# DIGITAL_IO.net
KiCad netlist of a schematic drawn in Altium Designer
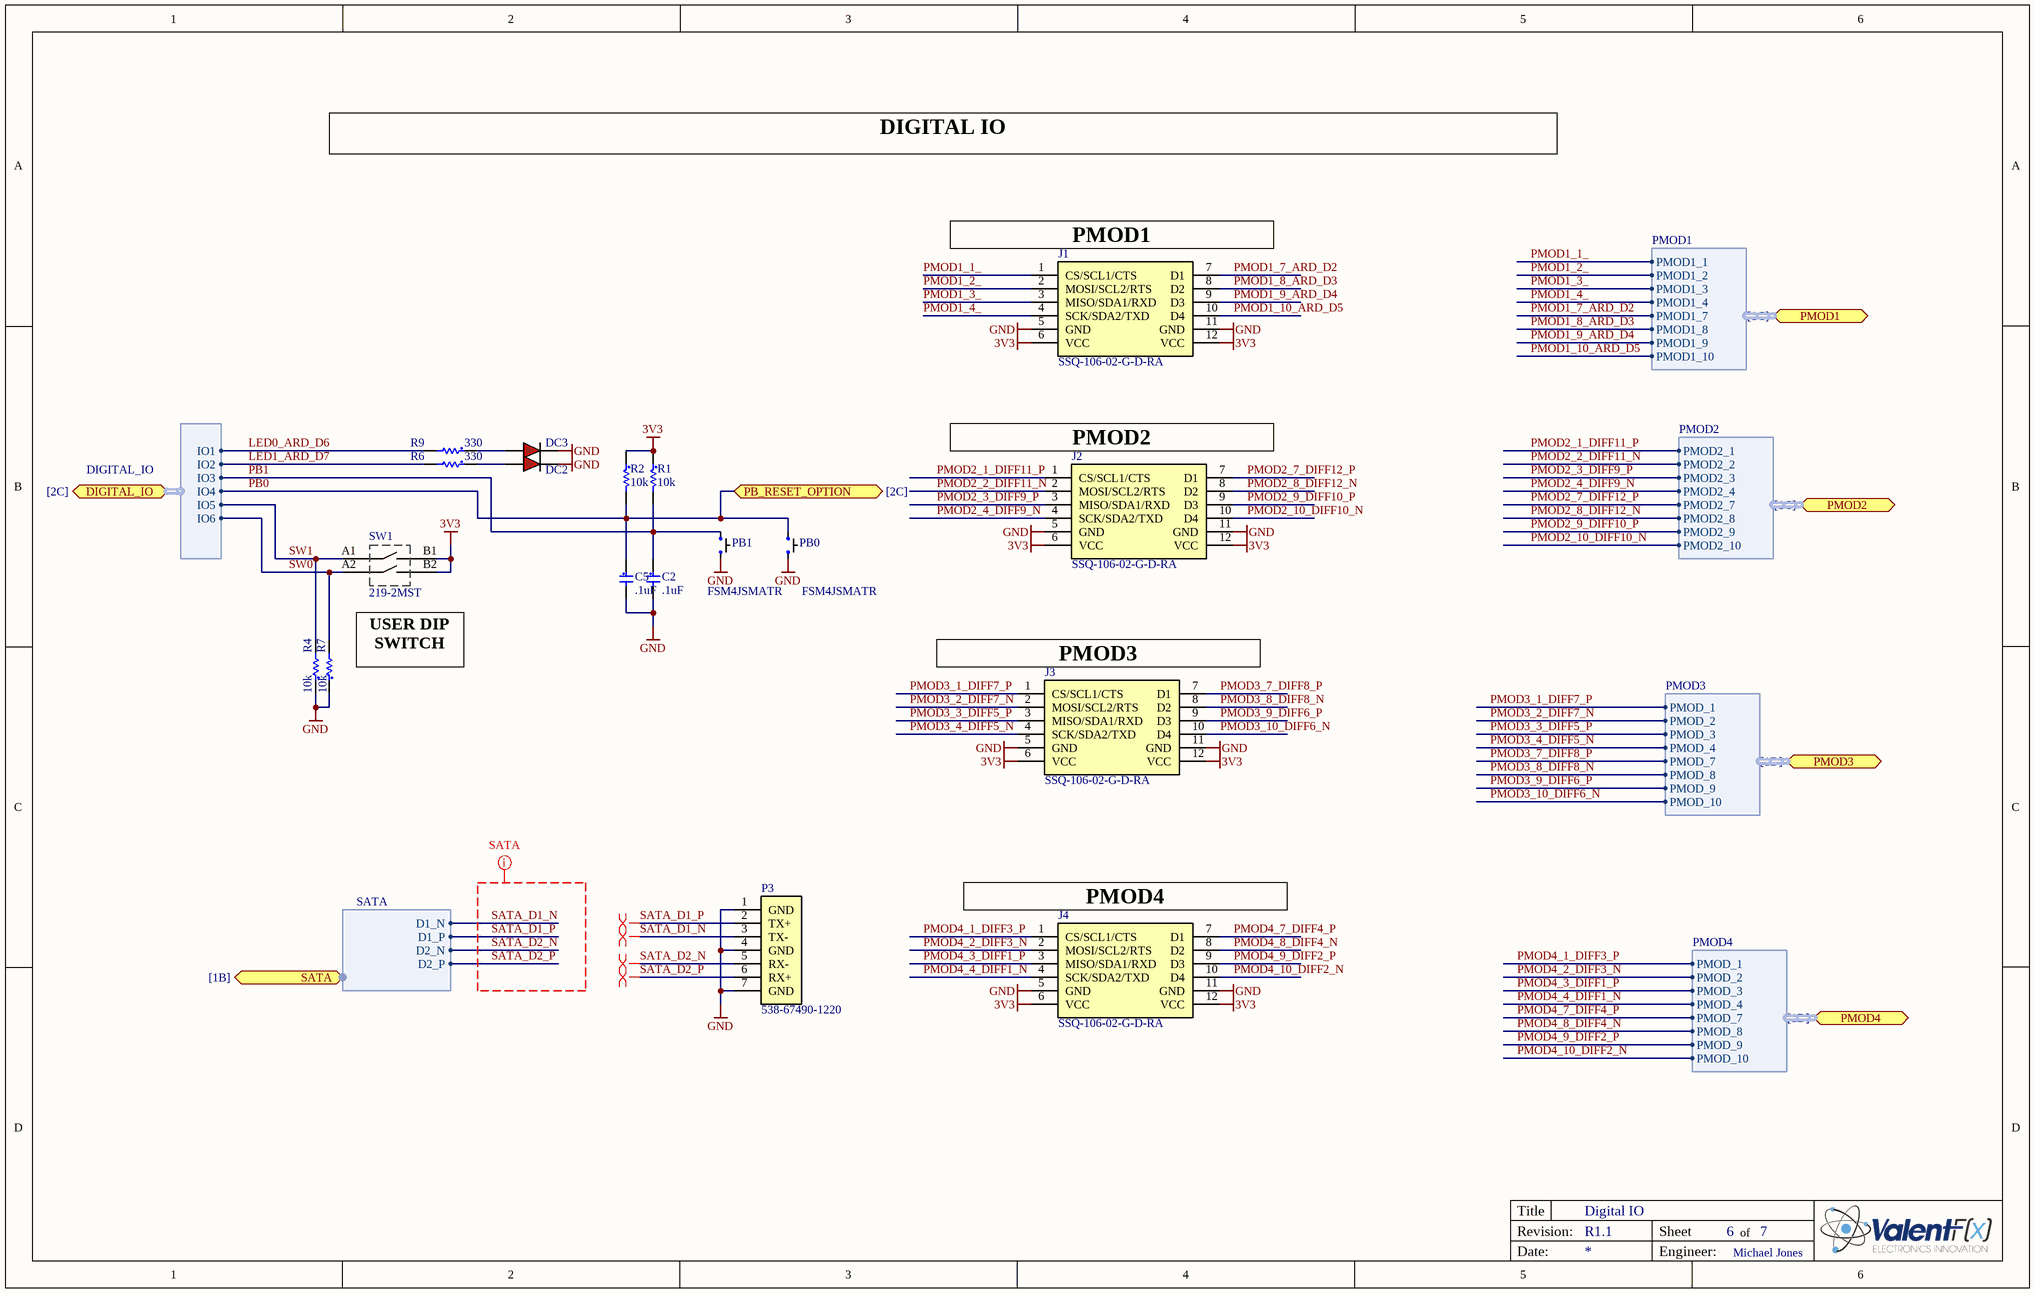
[diagram p0: DIGITAL_IO.SchDoc]

(export (version "E")
  (design (tool "Eeschema 10.0.6"))
  (components
    (comp (ref "C2")
      (value ".1uF")
      (footprint "c0603")
      (description "CAP CER 0.1UF 25V Y5V 0603")
      (fields
        (field (name "MANUFACTURER") "Samsung Electro-Mechanics America, Inc")
        (field (name "MANUFACTURER PART NUMBER") "CL10F104ZA8NNNC")
      )
      (libsource (lib "mCapacitors") (part "C0603 - CL10F104ZA8NNNC"))
    )
    (comp (ref "C5")
      (value ".1uF")
      (footprint "c0603")
      (description "CAP CER 0.1UF 25V Y5V 0603")
      (fields
        (field (name "MANUFACTURER") "Samsung Electro-Mechanics America, Inc")
        (field (name "MANUFACTURER PART NUMBER") "CL10F104ZA8NNNC")
      )
      (libsource (lib "mCapacitors") (part "C0603 - CL10F104ZA8NNNC"))
    )
    (comp (ref "DC2")
      (value "598-8010-107F")
      (footprint "LED_0603 - RED")
      (description "LED ALINGAP RED CLEAR 0603 SMD")
      (fields (field (name "MANUFACTURER") "Dialight"))
      (libsource (lib "mDiode") (part "LED0603 - 598-8010-107F"))
    )
    (comp (ref "DC3")
      (value "598-8010-107F")
      (footprint "LED_0603 - RED")
      (description "LED ALINGAP RED CLEAR 0603 SMD")
      (fields (field (name "MANUFACTURER") "Dialight"))
      (libsource (lib "mDiode") (part "LED0603 - 598-8010-107F"))
    )
    (comp (ref "J1")
      (value "SSQ-106-02-G-D-RA")
      (footprint "PMOD HEADER - SSQ-106-02-G-D-RA")
      (description "SAMTEC - SSQ-106-02-G-D-RA-005 - 2MM SOCKET STRIPS")
      (fields (field (name "MANUFACTURER") "SAMTEC"))
      (libsource (lib "mConnector") (part "P-MOD - SSQ-106-02-G-D-RA"))
    )
    (comp (ref "J2")
      (value "SSQ-106-02-G-D-RA")
      (footprint "PMOD HEADER - SSQ-106-02-G-D-RA")
      (description "SAMTEC - SSQ-106-02-G-D-RA-005 - 2MM SOCKET STRIPS")
      (fields (field (name "MANUFACTURER") "SAMTEC"))
      (libsource (lib "mConnector") (part "P-MOD - SSQ-106-02-G-D-RA"))
    )
    (comp (ref "J3")
      (value "SSQ-106-02-G-D-RA")
      (footprint "PMOD HEADER - SSQ-106-02-G-D-RA")
      (description "SAMTEC - SSQ-106-02-G-D-RA-005 - 2MM SOCKET STRIPS")
      (fields (field (name "MANUFACTURER") "SAMTEC"))
      (libsource (lib "mConnector") (part "P-MOD - SSQ-106-02-G-D-RA"))
    )
    (comp (ref "J4")
      (value "SSQ-106-02-G-D-RA")
      (footprint "PMOD HEADER - SSQ-106-02-G-D-RA")
      (description "SAMTEC - SSQ-106-02-G-D-RA-005 - 2MM SOCKET STRIPS")
      (fields (field (name "MANUFACTURER") "SAMTEC"))
      (libsource (lib "mConnector") (part "P-MOD - SSQ-106-02-G-D-RA"))
    )
    (comp (ref "P3")
      (value "SATA - 67490-1220")
      (footprint "SATA - 67490-3220")
      (description "SATA Data - 67490-1220")
      (fields
        (field (name "MANUFACTURER") "Molex")
        (field (name "MANUFACTURER PART NUMBER") "67490-1220")
        (field (name "SUPPLIER PART NUMBER 1") "538-67490-1220")
      )
      (libsource (lib "mConnector") (part "SATA - 67490-1220"))
    )
    (comp (ref "PB0")
      (value "FSM4JSMATR")
      (footprint "mElectroMechanical:FSM4JSMA")
      (description "SWITCH TACTILE SPST-NO 0.05A 12V")
      (fields
        (field (name "MANUFACTURER") "TE Connectivity")
        (field (name "MANUFACTURER PART NUMBER") "FSM4JSMA")
      )
      (libsource (lib "mElectroMechanical") (part "FSM4JSMATR"))
    )
    (comp (ref "PB1")
      (value "FSM4JSMATR")
      (footprint "mElectroMechanical:FSM4JSMA")
      (description "SWITCH TACTILE SPST-NO 0.05A 12V")
      (fields
        (field (name "MANUFACTURER") "TE Connectivity")
        (field (name "MANUFACTURER PART NUMBER") "FSM4JSMA")
      )
      (libsource (lib "mElectroMechanical") (part "FSM4JSMATR"))
    )
    (comp (ref "R1")
      (value "10k")
      (footprint "mRCL:R0603")
      (description "10k Thick Film Resistors - SMD 1/10watt 10Kohms 1%")
      (fields
        (field (name "MANUFACTURER") "Vishay Dale")
        (field (name "MANUFACTURER PART NUMBER") "CRCW060310K0FKEA")
      )
      (libsource (lib "mResistors") (part "R0603 - CRCW060310K0FKEA"))
    )
    (comp (ref "R2")
      (value "10k")
      (footprint "mRCL:R0603")
      (description "10k Thick Film Resistors - SMD 1/10watt 10Kohms 1%")
      (fields
        (field (name "MANUFACTURER") "Vishay Dale")
        (field (name "MANUFACTURER PART NUMBER") "CRCW060310K0FKEA")
      )
      (libsource (lib "mResistors") (part "R0603 - CRCW060310K0FKEA"))
    )
    (comp (ref "R4")
      (value "10k")
      (footprint "mRCL:R0603")
      (description "10k Thick Film Resistors - SMD 1/10watt 10Kohms 1%")
      (fields
        (field (name "MANUFACTURER") "Vishay Dale")
        (field (name "MANUFACTURER PART NUMBER") "CRCW060310K0FKEA")
      )
      (libsource (lib "") (part "R0603 - CRCW060310K0FKEA_1"))
    )
    (comp (ref "R6")
      (value "330")
      (footprint "R0603")
      (description "Thick Film Resistors - SMD 0603 330ohms 5% Tol")
      (fields
        (field (name "MANUFACTURER") "Panasonic")
        (field (name "MANUFACTURER PART NUMBER") "ERJ-3GEYJ331V")
      )
      (libsource (lib "mResistors") (part "R0603 - ERJ-3GEYJ331V"))
    )
    (comp (ref "R7")
      (value "10k")
      (footprint "mRCL:R0603")
      (description "10k Thick Film Resistors - SMD 1/10watt 10Kohms 1%")
      (fields
        (field (name "MANUFACTURER") "Vishay Dale")
        (field (name "MANUFACTURER PART NUMBER") "CRCW060310K0FKEA")
      )
      (libsource (lib "") (part "R0603 - CRCW060310K0FKEA_1"))
    )
    (comp (ref "R9")
      (value "330")
      (footprint "R0603")
      (description "Thick Film Resistors - SMD 0603 330ohms 5% Tol")
      (fields
        (field (name "MANUFACTURER") "Panasonic")
        (field (name "MANUFACTURER PART NUMBER") "ERJ-3GEYJ331V")
      )
      (libsource (lib "mResistors") (part "R0603 - ERJ-3GEYJ331V"))
    )
    (comp (ref "SW1")
      (value "219-2MST")
      (footprint "DIPSW - 219-2MST")
      (description "DIP Switches / SIP Switches SPST 2 switch sections")
      (fields (field (name "MANUFACTURER") "CTS Electronic Components"))
      (libsource (lib "mElectroMechanical") (part "DIPSW - 219-2MST"))
    )
  )
  (nets
    (net (code "7") (name "/LED0_ARD_D6") (class "Default")
      (node (ref "R9") (pin "2") (pinfunction "2_2") (pintype "passive"))
    )
    (net (code "8") (name "/LED1_ARD_D7") (class "Default")
      (node (ref "R6") (pin "2") (pinfunction "2_2") (pintype "passive"))
    )
    (net (code "9") (name "/PB0") (class "Default")
      (node (ref "C5") (pin "1") (pinfunction "1_1") (pintype "passive"))
      (node (ref "PB0") (pin "B") (pinfunction "B_B") (pintype "passive"))
      (node (ref "R2") (pin "2") (pinfunction "2_2") (pintype "passive"))
    )
    (net (code "10") (name "/PB1") (class "Default")
      (node (ref "C2") (pin "1") (pinfunction "1_1") (pintype "passive"))
      (node (ref "PB1") (pin "B") (pinfunction "B_B") (pintype "passive"))
      (node (ref "R1") (pin "2") (pinfunction "2_2") (pintype "passive"))
    )
    (net (code "11") (name "/PMOD1_1_") (class "Default")
      (node (ref "J1") (pin "1") (pinfunction "CS/SCL1/CTS_1") (pintype "power_in"))
    )
    (net (code "12") (name "/PMOD1_2_") (class "Default")
      (node (ref "J1") (pin "2") (pinfunction "MOSI/SCL2/RTS_2") (pintype "power_in"))
    )
    (net (code "13") (name "/PMOD1_3_") (class "Default")
      (node (ref "J1") (pin "3") (pinfunction "MISO/SDA1/RXD_3") (pintype "power_in"))
    )
    (net (code "14") (name "/PMOD1_4_") (class "Default")
      (node (ref "J1") (pin "4") (pinfunction "SCK/SDA2/TXD_4") (pintype "power_in"))
    )
    (net (code "15") (name "/PMOD1_7_ARD_D2") (class "Default")
      (node (ref "J1") (pin "7") (pinfunction "D1_7") (pintype "power_in"))
    )
    (net (code "16") (name "/PMOD1_8_ARD_D3") (class "Default")
      (node (ref "J1") (pin "8") (pinfunction "D2_8") (pintype "power_in"))
    )
    (net (code "17") (name "/PMOD1_9_ARD_D4") (class "Default")
      (node (ref "J1") (pin "9") (pinfunction "D3_9") (pintype "power_in"))
    )
    (net (code "18") (name "/PMOD1_10_ARD_D5") (class "Default")
      (node (ref "J1") (pin "10") (pinfunction "D4_10") (pintype "power_in"))
    )
    (net (code "19") (name "/PMOD2_1_DIFF11_P") (class "Default")
      (node (ref "J2") (pin "1") (pinfunction "CS/SCL1/CTS_1") (pintype "power_in"))
    )
    (net (code "20") (name "/PMOD2_2_DIFF11_N") (class "Default")
      (node (ref "J2") (pin "2") (pinfunction "MOSI/SCL2/RTS_2") (pintype "power_in"))
    )
    (net (code "21") (name "/PMOD2_3_DIFF9_P") (class "Default")
      (node (ref "J2") (pin "3") (pinfunction "MISO/SDA1/RXD_3") (pintype "power_in"))
    )
    (net (code "22") (name "/PMOD2_4_DIFF9_N") (class "Default")
      (node (ref "J2") (pin "4") (pinfunction "SCK/SDA2/TXD_4") (pintype "power_in"))
    )
    (net (code "23") (name "/PMOD2_7_DIFF12_P") (class "Default")
      (node (ref "J2") (pin "7") (pinfunction "D1_7") (pintype "power_in"))
    )
    (net (code "24") (name "/PMOD2_8_DIFF12_N") (class "Default")
      (node (ref "J2") (pin "8") (pinfunction "D2_8") (pintype "power_in"))
    )
    (net (code "25") (name "/PMOD2_9_DIFF10_P") (class "Default")
      (node (ref "J2") (pin "9") (pinfunction "D3_9") (pintype "power_in"))
    )
    (net (code "26") (name "/PMOD2_10_DIFF10_N") (class "Default")
      (node (ref "J2") (pin "10") (pinfunction "D4_10") (pintype "power_in"))
    )
    (net (code "27") (name "/PMOD3_1_DIFF7_P") (class "Default")
      (node (ref "J3") (pin "1") (pinfunction "CS/SCL1/CTS_1") (pintype "power_in"))
    )
    (net (code "28") (name "/PMOD3_2_DIFF7_N") (class "Default")
      (node (ref "J3") (pin "2") (pinfunction "MOSI/SCL2/RTS_2") (pintype "power_in"))
    )
    (net (code "29") (name "/PMOD3_3_DIFF5_P") (class "Default")
      (node (ref "J3") (pin "3") (pinfunction "MISO/SDA1/RXD_3") (pintype "power_in"))
    )
    (net (code "30") (name "/PMOD3_4_DIFF5_N") (class "Default")
      (node (ref "J3") (pin "4") (pinfunction "SCK/SDA2/TXD_4") (pintype "power_in"))
    )
    (net (code "31") (name "/PMOD3_7_DIFF8_P") (class "Default")
      (node (ref "J3") (pin "7") (pinfunction "D1_7") (pintype "power_in"))
    )
    (net (code "32") (name "/PMOD3_8_DIFF8_N") (class "Default")
      (node (ref "J3") (pin "8") (pinfunction "D2_8") (pintype "power_in"))
    )
    (net (code "33") (name "/PMOD3_9_DIFF6_P") (class "Default")
      (node (ref "J3") (pin "9") (pinfunction "D3_9") (pintype "power_in"))
    )
    (net (code "34") (name "/PMOD3_10_DIFF6_N") (class "Default")
      (node (ref "J3") (pin "10") (pinfunction "D4_10") (pintype "power_in"))
    )
    (net (code "35") (name "/PMOD4_1_DIFF3_P") (class "Default")
      (node (ref "J4") (pin "1") (pinfunction "CS/SCL1/CTS_1") (pintype "power_in"))
    )
    (net (code "36") (name "/PMOD4_2_DIFF3_N") (class "Default")
      (node (ref "J4") (pin "2") (pinfunction "MOSI/SCL2/RTS_2") (pintype "power_in"))
    )
    (net (code "37") (name "/PMOD4_3_DIFF1_P") (class "Default")
      (node (ref "J4") (pin "3") (pinfunction "MISO/SDA1/RXD_3") (pintype "power_in"))
    )
    (net (code "38") (name "/PMOD4_4_DIFF1_N") (class "Default")
      (node (ref "J4") (pin "4") (pinfunction "SCK/SDA2/TXD_4") (pintype "power_in"))
    )
    (net (code "39") (name "/PMOD4_7_DIFF4_P") (class "Default")
      (node (ref "J4") (pin "7") (pinfunction "D1_7") (pintype "power_in"))
    )
    (net (code "40") (name "/PMOD4_8_DIFF4_N") (class "Default")
      (node (ref "J4") (pin "8") (pinfunction "D2_8") (pintype "power_in"))
    )
    (net (code "41") (name "/PMOD4_9_DIFF2_P") (class "Default")
      (node (ref "J4") (pin "9") (pinfunction "D3_9") (pintype "power_in"))
    )
    (net (code "42") (name "/PMOD4_10_DIFF2_N") (class "Default")
      (node (ref "J4") (pin "10") (pinfunction "D4_10") (pintype "power_in"))
    )
    (net (code "43") (name "/SATA_D1_N") (class "Default")
      (node (ref "P3") (pin "3") (pinfunction "TX-_3") (pintype "passive"))
    )
    (net (code "44") (name "/SATA_D1_P") (class "Default")
      (node (ref "P3") (pin "2") (pinfunction "TX+_2") (pintype "passive"))
    )
    (net (code "45") (name "/SATA_D2_N") (class "Default")
      (node (ref "P3") (pin "5") (pinfunction "RX-_5") (pintype "passive"))
    )
    (net (code "46") (name "/SATA_D2_P") (class "Default")
      (node (ref "P3") (pin "6") (pinfunction "RX+_6") (pintype "passive"))
    )
    (net (code "47") (name "/SW0") (class "Default")
      (node (ref "R7") (pin "2") (pinfunction "2_2") (pintype "passive"))
      (node (ref "SW1") (pin "A2") (pinfunction "A2_A2") (pintype "passive"))
    )
    (net (code "48") (name "/SW1") (class "Default")
      (node (ref "R4") (pin "2") (pinfunction "2_2") (pintype "passive"))
      (node (ref "SW1") (pin "A1") (pinfunction "A1_A1") (pintype "passive"))
    )
    (net (code "55") (name "3V3") (class "Default")
      (node (ref "J1") (pin "12") (pinfunction "VCC_12") (pintype "power_in"))
      (node (ref "J1") (pin "6") (pinfunction "VCC_6") (pintype "power_in"))
      (node (ref "J2") (pin "12") (pinfunction "VCC_12") (pintype "power_in"))
      (node (ref "J2") (pin "6") (pinfunction "VCC_6") (pintype "power_in"))
      (node (ref "J3") (pin "12") (pinfunction "VCC_12") (pintype "power_in"))
      (node (ref "J3") (pin "6") (pinfunction "VCC_6") (pintype "power_in"))
      (node (ref "J4") (pin "12") (pinfunction "VCC_12") (pintype "power_in"))
      (node (ref "J4") (pin "6") (pinfunction "VCC_6") (pintype "power_in"))
      (node (ref "R1") (pin "1") (pinfunction "1_1") (pintype "passive"))
      (node (ref "R2") (pin "1") (pinfunction "1_1") (pintype "passive"))
      (node (ref "SW1") (pin "B1") (pinfunction "B1_B1") (pintype "passive"))
      (node (ref "SW1") (pin "B2") (pinfunction "B2_B2") (pintype "passive"))
    )
    (net (code "56") (name "GND") (class "Default")
      (node (ref "C2") (pin "2") (pinfunction "2_2") (pintype "passive"))
      (node (ref "C5") (pin "2") (pinfunction "2_2") (pintype "passive"))
      (node (ref "DC2") (pin "C") (pinfunction "C_C") (pintype "passive"))
      (node (ref "DC3") (pin "C") (pinfunction "C_C") (pintype "passive"))
      (node (ref "J1") (pin "11") (pinfunction "GND_11") (pintype "power_in"))
      (node (ref "J1") (pin "5") (pinfunction "GND_5") (pintype "power_in"))
      (node (ref "J2") (pin "11") (pinfunction "GND_11") (pintype "power_in"))
      (node (ref "J2") (pin "5") (pinfunction "GND_5") (pintype "power_in"))
      (node (ref "J3") (pin "11") (pinfunction "GND_11") (pintype "power_in"))
      (node (ref "J3") (pin "5") (pinfunction "GND_5") (pintype "power_in"))
      (node (ref "J4") (pin "11") (pinfunction "GND_11") (pintype "power_in"))
      (node (ref "J4") (pin "5") (pinfunction "GND_5") (pintype "power_in"))
      (node (ref "P3") (pin "1") (pinfunction "GND_1") (pintype "passive"))
      (node (ref "P3") (pin "4") (pinfunction "GND_4") (pintype "passive"))
      (node (ref "P3") (pin "7") (pinfunction "GND_7") (pintype "passive"))
      (node (ref "PB0") (pin "A") (pinfunction "A_A") (pintype "passive"))
      (node (ref "PB1") (pin "A") (pinfunction "A_A") (pintype "passive"))
      (node (ref "R4") (pin "1") (pinfunction "1_1") (pintype "passive"))
      (node (ref "R7") (pin "1") (pinfunction "1_1") (pintype "passive"))
    )
    (net (code "57") (name "Net-(DC2-PadA)") (class "Default")
      (node (ref "DC2") (pin "A") (pinfunction "A_A") (pintype "passive"))
      (node (ref "R6") (pin "1") (pinfunction "1_1") (pintype "passive"))
    )
    (net (code "58") (name "Net-(DC3-PadA)") (class "Default")
      (node (ref "DC3") (pin "A") (pinfunction "A_A") (pintype "passive"))
      (node (ref "R9") (pin "1") (pinfunction "1_1") (pintype "passive"))
    )
  )
)
